# Li-Po_Rider_v1_3.net
KiCad netlist of a schematic drawn in EAGLE
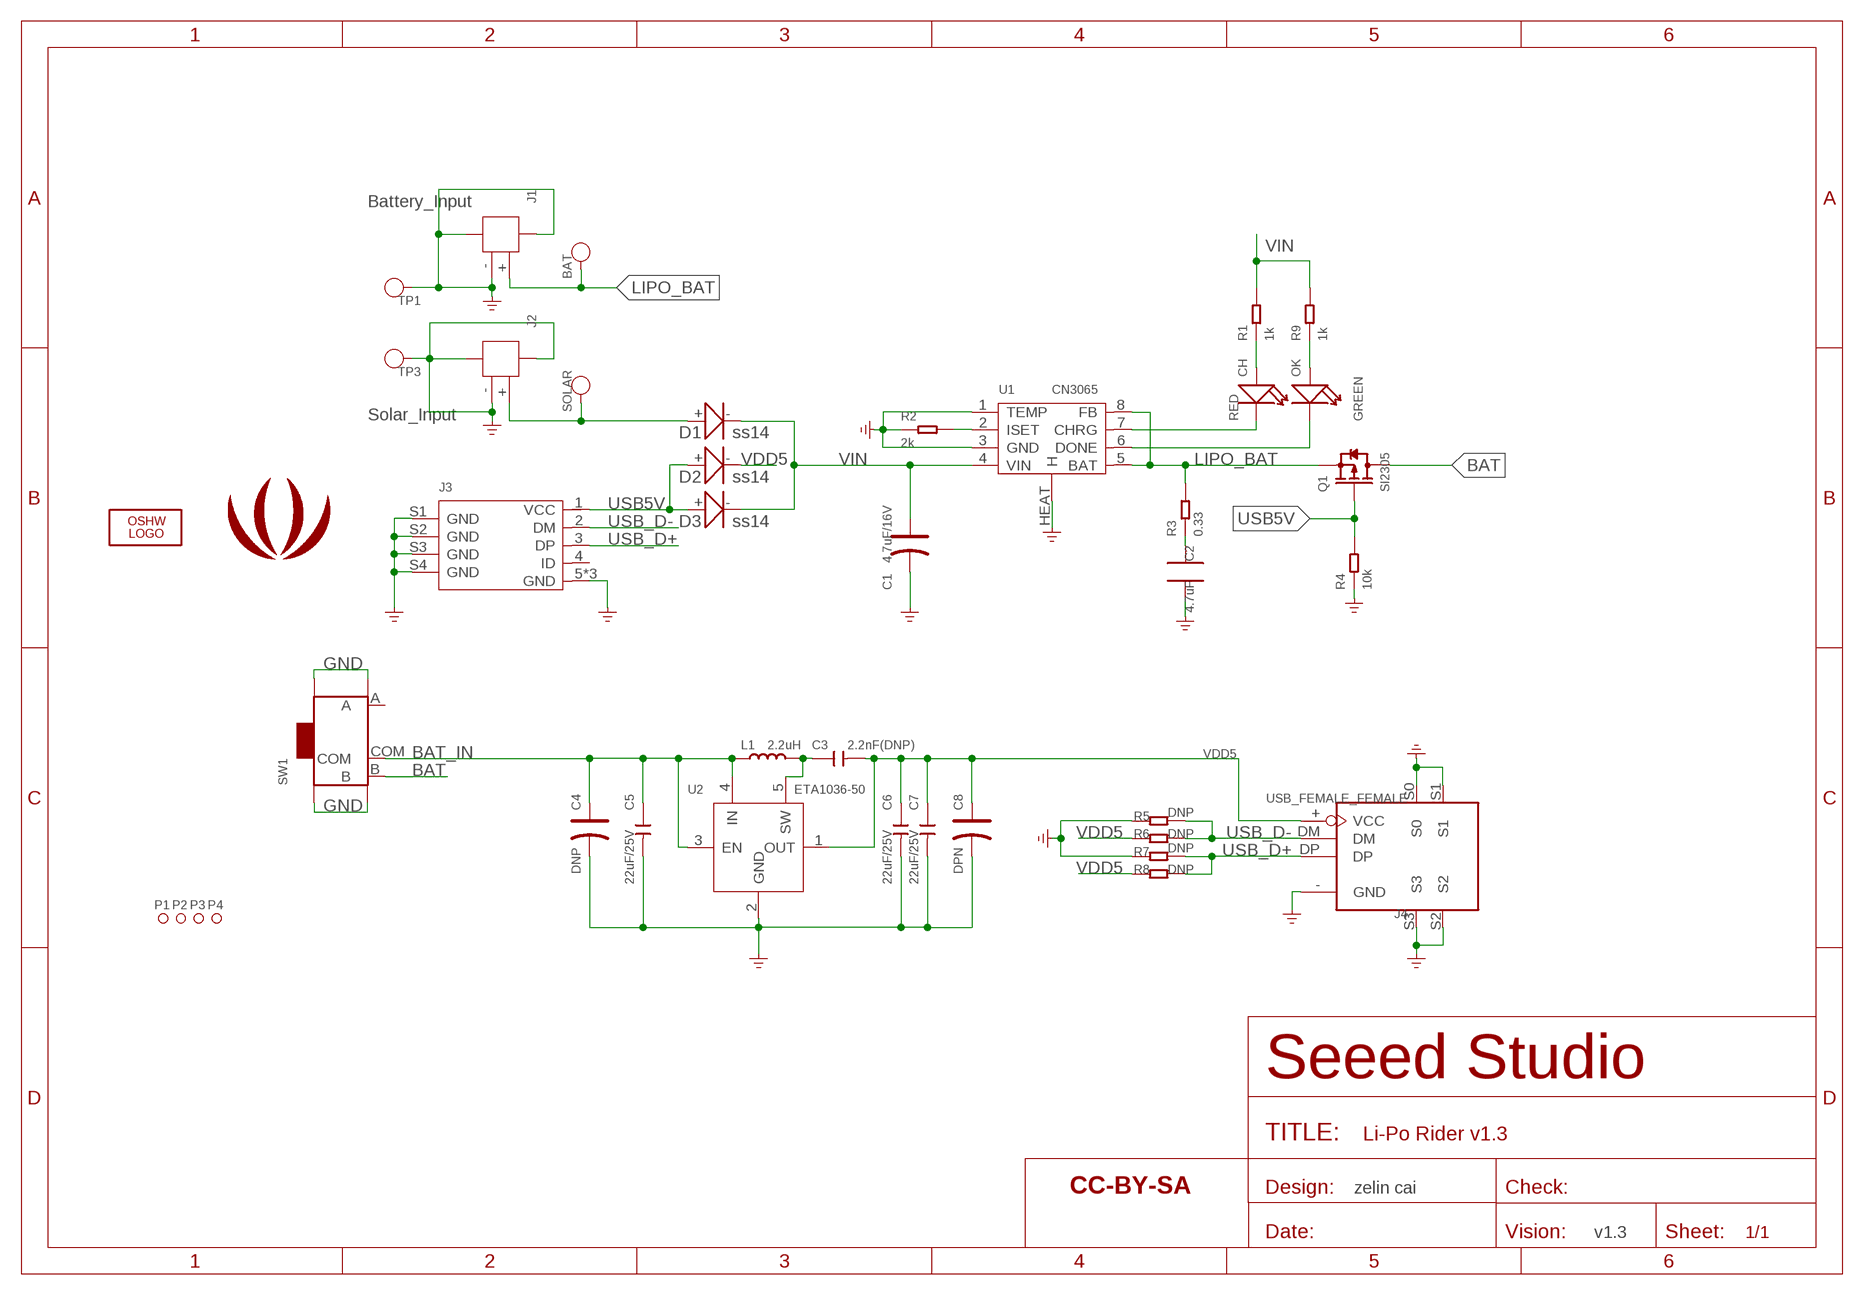
[diagram p0: schematic, sheet 1]

(export (version "E")
  (design (tool "Eeschema 10.0.6"))
  (components
    (comp (ref "BAT")
      (value "PAD-TEST-POINT'4545'")
      (footprint "eagle-import:TP-D45MIL")
      (fields (field (name "PARTNO") "DNP"))
      (libsource (lib "eagle-import") (part "PAD-TEST-POINT'4545'"))
    )
    (comp (ref "C1")
      (value "4.7uF/16V")
      (footprint "eagle-import:AVX_A")
      (libsource (lib "eagle-import") (part "006-CAP_AVX_A"))
    )
    (comp (ref "C2")
      (value "4.7uF")
      (footprint "eagle-import:0805")
      (libsource (lib "eagle-import") (part "C0805"))
    )
    (comp (ref "C3")
      (value "2.2nF(DNP)")
      (footprint "eagle-import:C0603")
      (libsource (lib "eagle-import") (part "C-0603"))
    )
    (comp (ref "C4")
      (value "DNP")
      (footprint "eagle-import:AVX-A")
      (libsource (lib "eagle-import") (part "CAP-AVX-A"))
    )
    (comp (ref "C5")
      (value "22uF/25V")
      (footprint "eagle-import:C0805")
      (libsource (lib "eagle-import") (part "CAP-0805"))
    )
    (comp (ref "C6")
      (value "22uF/25V")
      (footprint "eagle-import:C0805")
      (libsource (lib "eagle-import") (part "CAP-0805"))
    )
    (comp (ref "C7")
      (value "22uF/25V")
      (footprint "eagle-import:C0805")
      (libsource (lib "eagle-import") (part "CAP-0805"))
    )
    (comp (ref "C8")
      (value "DPN")
      (footprint "eagle-import:AVX-A")
      (libsource (lib "eagle-import") (part "CAP-AVX-A"))
    )
    (comp (ref "CH")
      (value "RED")
      (footprint "eagle-import:LED-0603")
      (libsource (lib "eagle-import") (part "LED'0603'"))
    )
    (comp (ref "D1")
      (value "ss14")
      (footprint "eagle-import:D2010")
      (libsource (lib "eagle-import") (part "010-D2010"))
    )
    (comp (ref "D2")
      (value "ss14")
      (footprint "eagle-import:D2010")
      (libsource (lib "eagle-import") (part "010-D2010"))
    )
    (comp (ref "D3")
      (value "ss14")
      (footprint "eagle-import:D2010")
      (libsource (lib "eagle-import") (part "010-D2010"))
    )
    (comp (ref "J1")
      (value "JST-2P-SMD'2.0'")
      (footprint "eagle-import:2P-SMD-2.0-90D")
      (libsource (lib "eagle-import") (part "JST-2P-SMD'2.0'"))
    )
    (comp (ref "J2")
      (value "JST-2P-SMD'2.0'")
      (footprint "eagle-import:2P-SMD-2.0-90D")
      (libsource (lib "eagle-import") (part "JST-2P-SMD'2.0'"))
    )
    (comp (ref "J3")
      (value "USB-MICRO-5P'5+4P'")
      (footprint "eagle-import:5+4P-SMD-0.65-B")
      (libsource (lib "eagle-import") (part "USB-MICRO-5P'5+4P'"))
    )
    (comp (ref "J4")
      (value "USB_FEMALE_FEMALE")
      (footprint "eagle-import:USB_FEMALE_HALF")
      (libsource (lib "eagle-import") (part "USB_FEMALEHHS"))
    )
    (comp (ref "L1")
      (value "2.2uH")
      (footprint "eagle-import:L0630")
      (libsource (lib "eagle-import") (part "INDUCTOR/FERRITE-BEAD'0630'"))
    )
    (comp (ref "LOGO1")
      (value "LOGO-OSHW-FILLX0200-NT")
      (footprint "eagle-import:OSHW_FILLX200_NOTEXT")
      (fields (field (name "PARTNO") "DNP"))
      (libsource (lib "eagle-import") (part "LOGO-OSHW-FILLX0200-NT"))
    )
    (comp (ref "OK")
      (value "GREEN")
      (footprint "eagle-import:LED-0603")
      (libsource (lib "eagle-import") (part "LED'0603'"))
    )
    (comp (ref "P1")
      (value "PAD-MARK'ANNULAR'")
      (footprint "eagle-import:ROUND-MARK-1.0")
      (fields (field (name "PARTNO") "DNP"))
      (libsource (lib "eagle-import") (part "PAD-MARK'ANNULAR'"))
    )
    (comp (ref "P2")
      (value "PAD-MARK'ANNULAR'")
      (footprint "eagle-import:ROUND-MARK-1.0")
      (fields (field (name "PARTNO") "DNP"))
      (libsource (lib "eagle-import") (part "PAD-MARK'ANNULAR'"))
    )
    (comp (ref "P3")
      (value "PAD-MARK'ANNULAR'")
      (footprint "eagle-import:ROUND-MARK-1.0")
      (fields (field (name "PARTNO") "DNP"))
      (libsource (lib "eagle-import") (part "PAD-MARK'ANNULAR'"))
    )
    (comp (ref "P4")
      (value "PAD-MARK'ANNULAR'")
      (footprint "eagle-import:ROUND-MARK-1.0")
      (fields (field (name "PARTNO") "DNP"))
      (libsource (lib "eagle-import") (part "PAD-MARK'ANNULAR'"))
    )
    (comp (ref "Q1")
      (value "SI2305")
      (footprint "eagle-import:SOT-23")
      (libsource (lib "eagle-import") (part "MOSFET-P'SI2323CDS/SI2305DS{lt}BR{gt}'"))
    )
    (comp (ref "R1")
      (value "1k")
      (footprint "eagle-import:R0603")
      (libsource (lib "eagle-import") (part "RES-0603"))
    )
    (comp (ref "R2")
      (value "2k")
      (footprint "eagle-import:R0603")
      (libsource (lib "eagle-import") (part "RES-0603"))
    )
    (comp (ref "R3")
      (value "0.33")
      (footprint "eagle-import:R0603")
      (libsource (lib "eagle-import") (part "RES-0603"))
    )
    (comp (ref "R4")
      (value "10k")
      (footprint "eagle-import:R0603")
      (libsource (lib "eagle-import") (part "RES-0603"))
    )
    (comp (ref "R5")
      (value "DNP")
      (footprint "eagle-import:0805")
      (libsource (lib "eagle-import") (part "005-R0805"))
    )
    (comp (ref "R6")
      (value "DNP")
      (footprint "eagle-import:0805")
      (libsource (lib "eagle-import") (part "005-R0805"))
    )
    (comp (ref "R7")
      (value "DNP")
      (footprint "eagle-import:0805")
      (libsource (lib "eagle-import") (part "005-R0805"))
    )
    (comp (ref "R8")
      (value "DNP")
      (footprint "eagle-import:0805")
      (libsource (lib "eagle-import") (part "005-R0805"))
    )
    (comp (ref "R9")
      (value "1k")
      (footprint "eagle-import:R0603")
      (libsource (lib "eagle-import") (part "RES-0603"))
    )
    (comp (ref "SOLAR")
      (value "PAD-TEST-POINT'4545'")
      (footprint "eagle-import:TP-D45MIL")
      (fields (field (name "PARTNO") "DNP"))
      (libsource (lib "eagle-import") (part "PAD-TEST-POINT'4545'"))
    )
    (comp (ref "SW1")
      (value "SWITCH-3+4P")
      (footprint "eagle-import:3+4P-SMD-L6.7_W2.7_H3.2MM")
      (libsource (lib "eagle-import") (part "SWITCH-3+4P"))
    )
    (comp (ref "TP1")
      (value "PAD-TEST-POINT'4545'")
      (footprint "eagle-import:TP-D45MIL")
      (fields (field (name "PARTNO") "DNP"))
      (libsource (lib "eagle-import") (part "PAD-TEST-POINT'4545'"))
    )
    (comp (ref "TP3")
      (value "PAD-TEST-POINT'4545'")
      (footprint "eagle-import:TP-D45MIL")
      (fields (field (name "PARTNO") "DNP"))
      (libsource (lib "eagle-import") (part "PAD-TEST-POINT'4545'"))
    )
    (comp (ref "U$1")
      (value "LOGO-SEEEDSTUDIO-SILK")
      (footprint "eagle-import:LOGO_SILK")
      (libsource (lib "eagle-import") (part "LOGO-SEEEDSTUDIO-SILK"))
    )
    (comp (ref "U$2")
      (value "SEEEDSTUDIO-OPEN-SCH-FRAME")
      (footprint "eagle-import:SEEEDSTUDIO-PCB-FRAME")
      (libsource (lib "eagle-import") (part "SEEEDSTUDIO-OPEN-SCH-FRAME"))
    )
    (comp (ref "U1")
      (value "CN3065")
      (footprint "eagle-import:DFN-8")
      (libsource (lib "eagle-import") (part "PMIC-CN3065-DFN8"))
    )
    (comp (ref "U2")
      (value "ETA1036-50")
      (footprint "eagle-import:SOT23-5")
      (libsource (lib "eagle-import") (part "ETA1036"))
    )
  )
  (nets
    (net (code "1") (name "/BAT_IN") (class "Default")
      (node (ref "C4") (pin "+") (pinfunction "+_+") (pintype "passive"))
      (node (ref "C5") (pin "1") (pinfunction "1_1") (pintype "passive"))
      (node (ref "L1") (pin "1") (pinfunction "1_1") (pintype "passive"))
      (node (ref "SW1") (pin "COM") (pinfunction "COM_COM") (pintype "bidirectional"))
      (node (ref "U2") (pin "3") (pinfunction "EN_3") (pintype "bidirectional"))
      (node (ref "U2") (pin "4") (pinfunction "IN_4") (pintype "bidirectional"))
    )
    (net (code "2") (name "/USB_D+") (class "Default")
      (node (ref "J3") (pin "3") (pinfunction "DP_3") (pintype "bidirectional"))
      (node (ref "J4") (pin "DP") (pinfunction "DP_DP") (pintype "bidirectional"))
      (node (ref "R7") (pin "1") (pinfunction "1_1") (pintype "passive"))
      (node (ref "R8") (pin "1") (pinfunction "1_1") (pintype "passive"))
    )
    (net (code "3") (name "/USB_D-") (class "Default")
      (node (ref "J3") (pin "2") (pinfunction "DM_2") (pintype "bidirectional"))
      (node (ref "J4") (pin "DM") (pinfunction "DM_DM") (pintype "bidirectional"))
      (node (ref "R5") (pin "1") (pinfunction "1_1") (pintype "passive"))
      (node (ref "R6") (pin "1") (pinfunction "1_1") (pintype "passive"))
    )
    (net (code "4") (name "/VDD5") (class "Default")
      (node (ref "C3") (pin "2") (pinfunction "2_2") (pintype "passive"))
      (node (ref "C6") (pin "1") (pinfunction "1_1") (pintype "passive"))
      (node (ref "C7") (pin "1") (pinfunction "1_1") (pintype "passive"))
      (node (ref "C8") (pin "+") (pinfunction "+_+") (pintype "passive"))
      (node (ref "D2") (pin "-") (pinfunction "-_-") (pintype "passive"))
      (node (ref "J4") (pin "+") (pinfunction "VCC_+") (pintype "bidirectional"))
      (node (ref "R6") (pin "2") (pinfunction "2_2") (pintype "passive"))
      (node (ref "R8") (pin "2") (pinfunction "2_2") (pintype "passive"))
      (node (ref "U2") (pin "1") (pinfunction "OUT_1") (pintype "bidirectional"))
    )
    (net (code "5") (name "/VIN") (class "Default")
      (node (ref "C1") (pin "+") (pinfunction "+_+") (pintype "passive"))
      (node (ref "D1") (pin "-") (pinfunction "-_-") (pintype "passive"))
      (node (ref "D3") (pin "-") (pinfunction "-_-") (pintype "passive"))
      (node (ref "R1") (pin "2") (pinfunction "2_2") (pintype "passive"))
      (node (ref "R9") (pin "2") (pinfunction "2_2") (pintype "passive"))
      (node (ref "U1") (pin "4") (pinfunction "VIN_4") (pintype "input"))
    )
    (net (code "6") (name "BAT") (class "Default")
      (node (ref "Q1") (pin "3") (pinfunction "D_3") (pintype "passive"))
      (node (ref "SW1") (pin "B") (pinfunction "B_B") (pintype "bidirectional"))
    )
    (net (code "7") (name "GND_POWER") (class "Default")
      (node (ref "C1") (pin "-") (pinfunction "-_-") (pintype "passive"))
      (node (ref "C2") (pin "2") (pinfunction "2_2") (pintype "bidirectional"))
      (node (ref "C4") (pin "-") (pinfunction "-_-") (pintype "passive"))
      (node (ref "C5") (pin "2") (pinfunction "2_2") (pintype "passive"))
      (node (ref "C6") (pin "2") (pinfunction "2_2") (pintype "passive"))
      (node (ref "C7") (pin "2") (pinfunction "2_2") (pintype "passive"))
      (node (ref "C8") (pin "-") (pinfunction "-_-") (pintype "passive"))
      (node (ref "J1") (pin "-") (pinfunction "2_-") (pintype "bidirectional"))
      (node (ref "J1") (pin "3") (pinfunction "3_3") (pintype "bidirectional"))
      (node (ref "J1") (pin "4") (pinfunction "4_4") (pintype "bidirectional"))
      (node (ref "J2") (pin "-") (pinfunction "2_-") (pintype "bidirectional"))
      (node (ref "J2") (pin "3") (pinfunction "3_3") (pintype "bidirectional"))
      (node (ref "J2") (pin "4") (pinfunction "4_4") (pintype "bidirectional"))
      (node (ref "J3") (pin "5") (pinfunction "GND_5") (pintype "bidirectional"))
      (node (ref "J3") (pin "S1") (pinfunction "GND_S1") (pintype "bidirectional"))
      (node (ref "J3") (pin "S2") (pinfunction "GND_S2") (pintype "bidirectional"))
      (node (ref "J3") (pin "S3") (pinfunction "GND_S3") (pintype "bidirectional"))
      (node (ref "J3") (pin "S4") (pinfunction "GND_S4") (pintype "bidirectional"))
      (node (ref "J3") (pin "S5") (pinfunction "GND_S5") (pintype "bidirectional"))
      (node (ref "J3") (pin "S6") (pinfunction "GND_S6") (pintype "bidirectional"))
      (node (ref "J4") (pin "-") (pinfunction "GND_-") (pintype "bidirectional"))
      (node (ref "J4") (pin "S0") (pinfunction "S0_S0") (pintype "bidirectional"))
      (node (ref "J4") (pin "S1") (pinfunction "S1_S1") (pintype "bidirectional"))
      (node (ref "J4") (pin "S2") (pinfunction "S2_S2") (pintype "bidirectional"))
      (node (ref "J4") (pin "S3") (pinfunction "S3_S3") (pintype "bidirectional"))
      (node (ref "R2") (pin "1") (pinfunction "1_1") (pintype "passive"))
      (node (ref "R4") (pin "1") (pinfunction "1_1") (pintype "passive"))
      (node (ref "R5") (pin "2") (pinfunction "2_2") (pintype "passive"))
      (node (ref "R7") (pin "2") (pinfunction "2_2") (pintype "passive"))
      (node (ref "SW1") (pin "SS1") (pinfunction "SS1_SS1") (pintype "bidirectional"))
      (node (ref "SW1") (pin "SS2") (pinfunction "SS2_SS2") (pintype "bidirectional"))
      (node (ref "SW1") (pin "SS3") (pinfunction "SS3_SS3") (pintype "bidirectional"))
      (node (ref "SW1") (pin "SS4") (pinfunction "SS4_SS4") (pintype "bidirectional"))
      (node (ref "TP1") (pin "T") (pinfunction "T_T") (pintype "bidirectional"))
      (node (ref "TP3") (pin "T") (pinfunction "T_T") (pintype "bidirectional"))
      (node (ref "U1") (pin "1") (pinfunction "TEMP_1") (pintype "input"))
      (node (ref "U1") (pin "3") (pinfunction "GND_3") (pintype "power_in"))
      (node (ref "U1") (pin "HEAT") (pinfunction "H_HEAT") (pintype "bidirectional"))
      (node (ref "U2") (pin "2") (pinfunction "GND_2") (pintype "bidirectional"))
    )
    (net (code "8") (name "LIPO_BAT") (class "Default")
      (node (ref "BAT") (pin "T") (pinfunction "T_T") (pintype "bidirectional"))
      (node (ref "J1") (pin "+") (pinfunction "1_+") (pintype "bidirectional"))
      (node (ref "Q1") (pin "2") (pinfunction "S_2") (pintype "passive"))
      (node (ref "R3") (pin "2") (pinfunction "2_2") (pintype "passive"))
      (node (ref "U1") (pin "5") (pinfunction "BAT_5") (pintype "bidirectional"))
      (node (ref "U1") (pin "8") (pinfunction "FB_8") (pintype "input"))
    )
    (net (code "9") (name "Net-(C2-Pad1)") (class "Default")
      (node (ref "C2") (pin "1") (pinfunction "1_1") (pintype "bidirectional"))
      (node (ref "R3") (pin "1") (pinfunction "1_1") (pintype "passive"))
    )
    (net (code "10") (name "Net-(CH-Pad+)") (class "Default")
      (node (ref "CH") (pin "+") (pinfunction "+_+") (pintype "passive"))
      (node (ref "R1") (pin "1") (pinfunction "1_1") (pintype "passive"))
    )
    (net (code "11") (name "Net-(J2-1)") (class "Default")
      (node (ref "D1") (pin "+") (pinfunction "+_+") (pintype "passive"))
      (node (ref "J2") (pin "+") (pinfunction "1_+") (pintype "bidirectional"))
      (node (ref "SOLAR") (pin "T") (pinfunction "T_T") (pintype "bidirectional"))
    )
    (net (code "12") (name "Net-(OK-Pad+)") (class "Default")
      (node (ref "OK") (pin "+") (pinfunction "+_+") (pintype "passive"))
      (node (ref "R9") (pin "1") (pinfunction "1_1") (pintype "passive"))
    )
    (net (code "13") (name "Net-(U1-CHRG)") (class "Default")
      (node (ref "CH") (pin "-") (pinfunction "-_-") (pintype "passive"))
      (node (ref "U1") (pin "7") (pinfunction "CHRG_7") (pintype "bidirectional"))
    )
    (net (code "14") (name "Net-(U1-DONE)") (class "Default")
      (node (ref "OK") (pin "-") (pinfunction "-_-") (pintype "passive"))
      (node (ref "U1") (pin "6") (pinfunction "DONE_6") (pintype "bidirectional"))
    )
    (net (code "15") (name "Net-(U1-ISET)") (class "Default")
      (node (ref "R2") (pin "2") (pinfunction "2_2") (pintype "passive"))
      (node (ref "U1") (pin "2") (pinfunction "ISET_2") (pintype "bidirectional"))
    )
    (net (code "16") (name "Net-(U2-SW)") (class "Default")
      (node (ref "C3") (pin "1") (pinfunction "1_1") (pintype "passive"))
      (node (ref "L1") (pin "2") (pinfunction "2_2") (pintype "passive"))
      (node (ref "U2") (pin "5") (pinfunction "SW_5") (pintype "bidirectional"))
    )
    (net (code "17") (name "USB5V") (class "Default")
      (node (ref "D2") (pin "+") (pinfunction "+_+") (pintype "passive"))
      (node (ref "D3") (pin "+") (pinfunction "+_+") (pintype "passive"))
      (node (ref "J3") (pin "1") (pinfunction "VCC_1") (pintype "bidirectional"))
      (node (ref "Q1") (pin "1") (pinfunction "G_1") (pintype "passive"))
      (node (ref "R4") (pin "2") (pinfunction "2_2") (pintype "passive"))
    )
    (net (code "18") (name "unconnected-(J3-ID-Pad4)") (class "Default")
      (node (ref "J3") (pin "4") (pinfunction "ID_4") (pintype "bidirectional"))
    )
    (net (code "19") (name "unconnected-(SW1-PadA)") (class "Default")
      (node (ref "SW1") (pin "A") (pinfunction "A_A") (pintype "bidirectional"))
    )
  )
)
